# CurrentTransPCB.net
KiCad netlist of a schematic drawn in Altium Designer
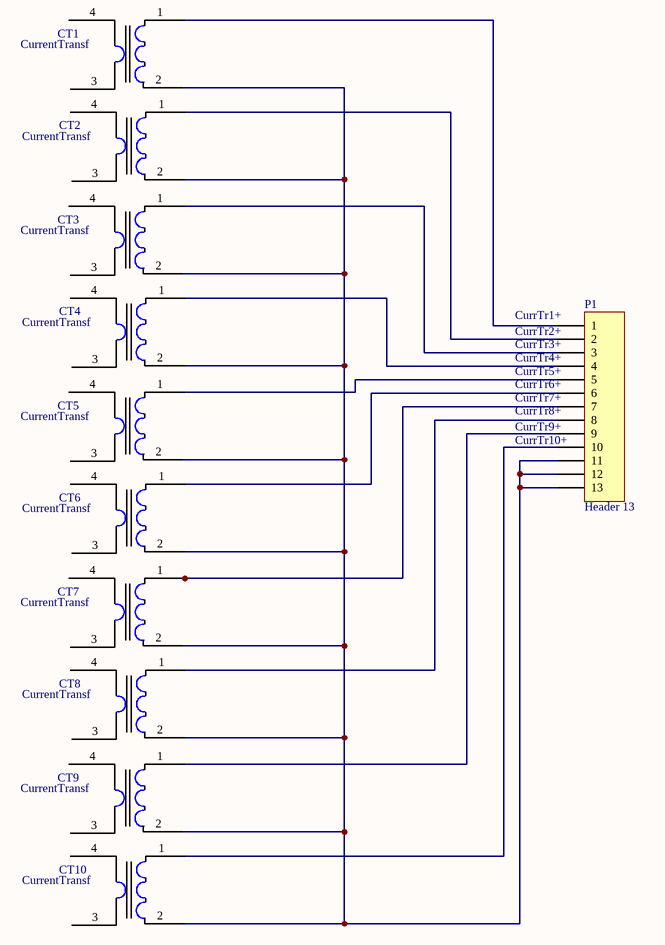
[diagram p0: CurrentTransPCB.SchDoc]

(export (version "E")
  (design (tool "Eeschema 10.0.6"))
  (components
    (comp (ref "CT1")
      (value "CurrentTransf")
      (footprint "CT-ZMCT124")
      (libsource (lib "SMLib") (part "CurrentTransf"))
    )
    (comp (ref "CT2")
      (value "CurrentTransf")
      (footprint "CT-ZMCT124")
      (libsource (lib "SMLib") (part "CurrentTransf"))
    )
    (comp (ref "CT3")
      (value "CurrentTransf")
      (footprint "CT-ZMCT124")
      (libsource (lib "SMLib") (part "CurrentTransf"))
    )
    (comp (ref "CT4")
      (value "CurrentTransf")
      (footprint "CT-ZMCT124")
      (libsource (lib "SMLib") (part "CurrentTransf"))
    )
    (comp (ref "CT5")
      (value "CurrentTransf")
      (footprint "CT-ZMCT124")
      (libsource (lib "SMLib") (part "CurrentTransf"))
    )
    (comp (ref "CT6")
      (value "CurrentTransf")
      (footprint "CT-ZMCT124")
      (libsource (lib "SMLib") (part "CurrentTransf"))
    )
    (comp (ref "CT7")
      (value "CurrentTransf")
      (footprint "CT-ZMCT124")
      (fields (field (name "MANUFACTURER") "NanJing ZeMing Electronics Co.Ltd"))
      (libsource (lib "SMLib") (part "CurrentTransf"))
    )
    (comp (ref "CT8")
      (value "CurrentTransf")
      (footprint "CT-ZMCT124")
      (libsource (lib "SMLib") (part "CurrentTransf"))
    )
    (comp (ref "CT9")
      (value "CurrentTransf")
      (footprint "CT-ZMCT124")
      (libsource (lib "SMLib") (part "CurrentTransf"))
    )
    (comp (ref "CT10")
      (value "CurrentTransf")
      (footprint "CT-ZMCT124")
      (libsource (lib "SMLib") (part "CurrentTransf"))
    )
    (comp (ref "P1")
      (value "Header 13")
      (footprint "HDR1X13")
      (description "Header, 13-Pin")
      (fields (field (name "PUBLISHER") "Altium Limited"))
      (libsource (lib "Miscellaneous Connectors") (part "Header 13"))
    )
  )
  (nets
    (net (code "1") (name "Net-(CT1-Pad1)") (class "Default")
      (node (ref "CT1") (pin "1") (pinfunction "1_1") (pintype "passive"))
      (node (ref "P1") (pin "1") (pinfunction "1_1") (pintype "passive"))
    )
    (net (code "2") (name "Net-(CT1-Pad2)") (class "Default")
      (node (ref "CT1") (pin "2") (pinfunction "2_2") (pintype "passive"))
      (node (ref "CT10") (pin "2") (pinfunction "2_2") (pintype "passive"))
      (node (ref "CT2") (pin "2") (pinfunction "2_2") (pintype "passive"))
      (node (ref "CT3") (pin "2") (pinfunction "2_2") (pintype "passive"))
      (node (ref "CT4") (pin "2") (pinfunction "2_2") (pintype "passive"))
      (node (ref "CT5") (pin "2") (pinfunction "2_2") (pintype "passive"))
      (node (ref "CT6") (pin "2") (pinfunction "2_2") (pintype "passive"))
      (node (ref "CT7") (pin "2") (pinfunction "2_2") (pintype "passive"))
      (node (ref "CT8") (pin "2") (pinfunction "2_2") (pintype "passive"))
      (node (ref "CT9") (pin "2") (pinfunction "2_2") (pintype "passive"))
      (node (ref "P1") (pin "11") (pinfunction "11_11") (pintype "passive"))
      (node (ref "P1") (pin "12") (pinfunction "12_12") (pintype "passive"))
      (node (ref "P1") (pin "13") (pinfunction "13_13") (pintype "passive"))
    )
    (net (code "3") (name "Net-(CT2-Pad1)") (class "Default")
      (node (ref "CT2") (pin "1") (pinfunction "1_1") (pintype "passive"))
      (node (ref "P1") (pin "2") (pinfunction "2_2") (pintype "passive"))
    )
    (net (code "4") (name "Net-(CT3-Pad1)") (class "Default")
      (node (ref "CT3") (pin "1") (pinfunction "1_1") (pintype "passive"))
      (node (ref "P1") (pin "3") (pinfunction "3_3") (pintype "passive"))
    )
    (net (code "5") (name "Net-(CT4-Pad1)") (class "Default")
      (node (ref "CT4") (pin "1") (pinfunction "1_1") (pintype "passive"))
      (node (ref "P1") (pin "4") (pinfunction "4_4") (pintype "passive"))
    )
    (net (code "6") (name "Net-(CT5-Pad1)") (class "Default")
      (node (ref "CT5") (pin "1") (pinfunction "1_1") (pintype "passive"))
      (node (ref "P1") (pin "5") (pinfunction "5_5") (pintype "passive"))
    )
    (net (code "7") (name "Net-(CT6-Pad1)") (class "Default")
      (node (ref "CT6") (pin "1") (pinfunction "1_1") (pintype "passive"))
      (node (ref "P1") (pin "6") (pinfunction "6_6") (pintype "passive"))
    )
    (net (code "8") (name "Net-(CT7-Pad1)") (class "Default")
      (node (ref "CT7") (pin "1") (pinfunction "1_1") (pintype "passive"))
      (node (ref "P1") (pin "7") (pinfunction "7_7") (pintype "passive"))
    )
    (net (code "9") (name "Net-(CT8-Pad1)") (class "Default")
      (node (ref "CT8") (pin "1") (pinfunction "1_1") (pintype "passive"))
      (node (ref "P1") (pin "8") (pinfunction "8_8") (pintype "passive"))
    )
    (net (code "10") (name "Net-(CT9-Pad1)") (class "Default")
      (node (ref "CT9") (pin "1") (pinfunction "1_1") (pintype "passive"))
      (node (ref "P1") (pin "9") (pinfunction "9_9") (pintype "passive"))
    )
    (net (code "11") (name "Net-(CT10-Pad1)") (class "Default")
      (node (ref "CT10") (pin "1") (pinfunction "1_1") (pintype "passive"))
      (node (ref "P1") (pin "10") (pinfunction "10_10") (pintype "passive"))
    )
    (net (code "12") (name "unconnected-(CT1-Pad3)") (class "Default")
      (node (ref "CT1") (pin "3") (pinfunction "3_3") (pintype "passive"))
    )
    (net (code "13") (name "unconnected-(CT1-Pad4)") (class "Default")
      (node (ref "CT1") (pin "4") (pinfunction "4_4") (pintype "passive"))
    )
    (net (code "14") (name "unconnected-(CT2-Pad3)") (class "Default")
      (node (ref "CT2") (pin "3") (pinfunction "3_3") (pintype "passive"))
    )
    (net (code "15") (name "unconnected-(CT2-Pad4)") (class "Default")
      (node (ref "CT2") (pin "4") (pinfunction "4_4") (pintype "passive"))
    )
    (net (code "16") (name "unconnected-(CT3-Pad3)") (class "Default")
      (node (ref "CT3") (pin "3") (pinfunction "3_3") (pintype "passive"))
    )
    (net (code "17") (name "unconnected-(CT3-Pad4)") (class "Default")
      (node (ref "CT3") (pin "4") (pinfunction "4_4") (pintype "passive"))
    )
    (net (code "18") (name "unconnected-(CT4-Pad3)") (class "Default")
      (node (ref "CT4") (pin "3") (pinfunction "3_3") (pintype "passive"))
    )
    (net (code "19") (name "unconnected-(CT4-Pad4)") (class "Default")
      (node (ref "CT4") (pin "4") (pinfunction "4_4") (pintype "passive"))
    )
    (net (code "20") (name "unconnected-(CT5-Pad3)") (class "Default")
      (node (ref "CT5") (pin "3") (pinfunction "3_3") (pintype "passive"))
    )
    (net (code "21") (name "unconnected-(CT5-Pad4)") (class "Default")
      (node (ref "CT5") (pin "4") (pinfunction "4_4") (pintype "passive"))
    )
    (net (code "22") (name "unconnected-(CT6-Pad3)") (class "Default")
      (node (ref "CT6") (pin "3") (pinfunction "3_3") (pintype "passive"))
    )
    (net (code "23") (name "unconnected-(CT6-Pad4)") (class "Default")
      (node (ref "CT6") (pin "4") (pinfunction "4_4") (pintype "passive"))
    )
    (net (code "24") (name "unconnected-(CT7-Pad3)") (class "Default")
      (node (ref "CT7") (pin "3") (pinfunction "3_3") (pintype "passive"))
    )
    (net (code "25") (name "unconnected-(CT7-Pad4)") (class "Default")
      (node (ref "CT7") (pin "4") (pinfunction "4_4") (pintype "passive"))
    )
    (net (code "26") (name "unconnected-(CT8-Pad3)") (class "Default")
      (node (ref "CT8") (pin "3") (pinfunction "3_3") (pintype "passive"))
    )
    (net (code "27") (name "unconnected-(CT8-Pad4)") (class "Default")
      (node (ref "CT8") (pin "4") (pinfunction "4_4") (pintype "passive"))
    )
    (net (code "28") (name "unconnected-(CT9-Pad3)") (class "Default")
      (node (ref "CT9") (pin "3") (pinfunction "3_3") (pintype "passive"))
    )
    (net (code "29") (name "unconnected-(CT9-Pad4)") (class "Default")
      (node (ref "CT9") (pin "4") (pinfunction "4_4") (pintype "passive"))
    )
    (net (code "30") (name "unconnected-(CT10-Pad3)") (class "Default")
      (node (ref "CT10") (pin "3") (pinfunction "3_3") (pintype "passive"))
    )
    (net (code "31") (name "unconnected-(CT10-Pad4)") (class "Default")
      (node (ref "CT10") (pin "4") (pinfunction "4_4") (pintype "passive"))
    )
  )
)
